# TOP.net
KiCad netlist of a schematic drawn in Altium Designer
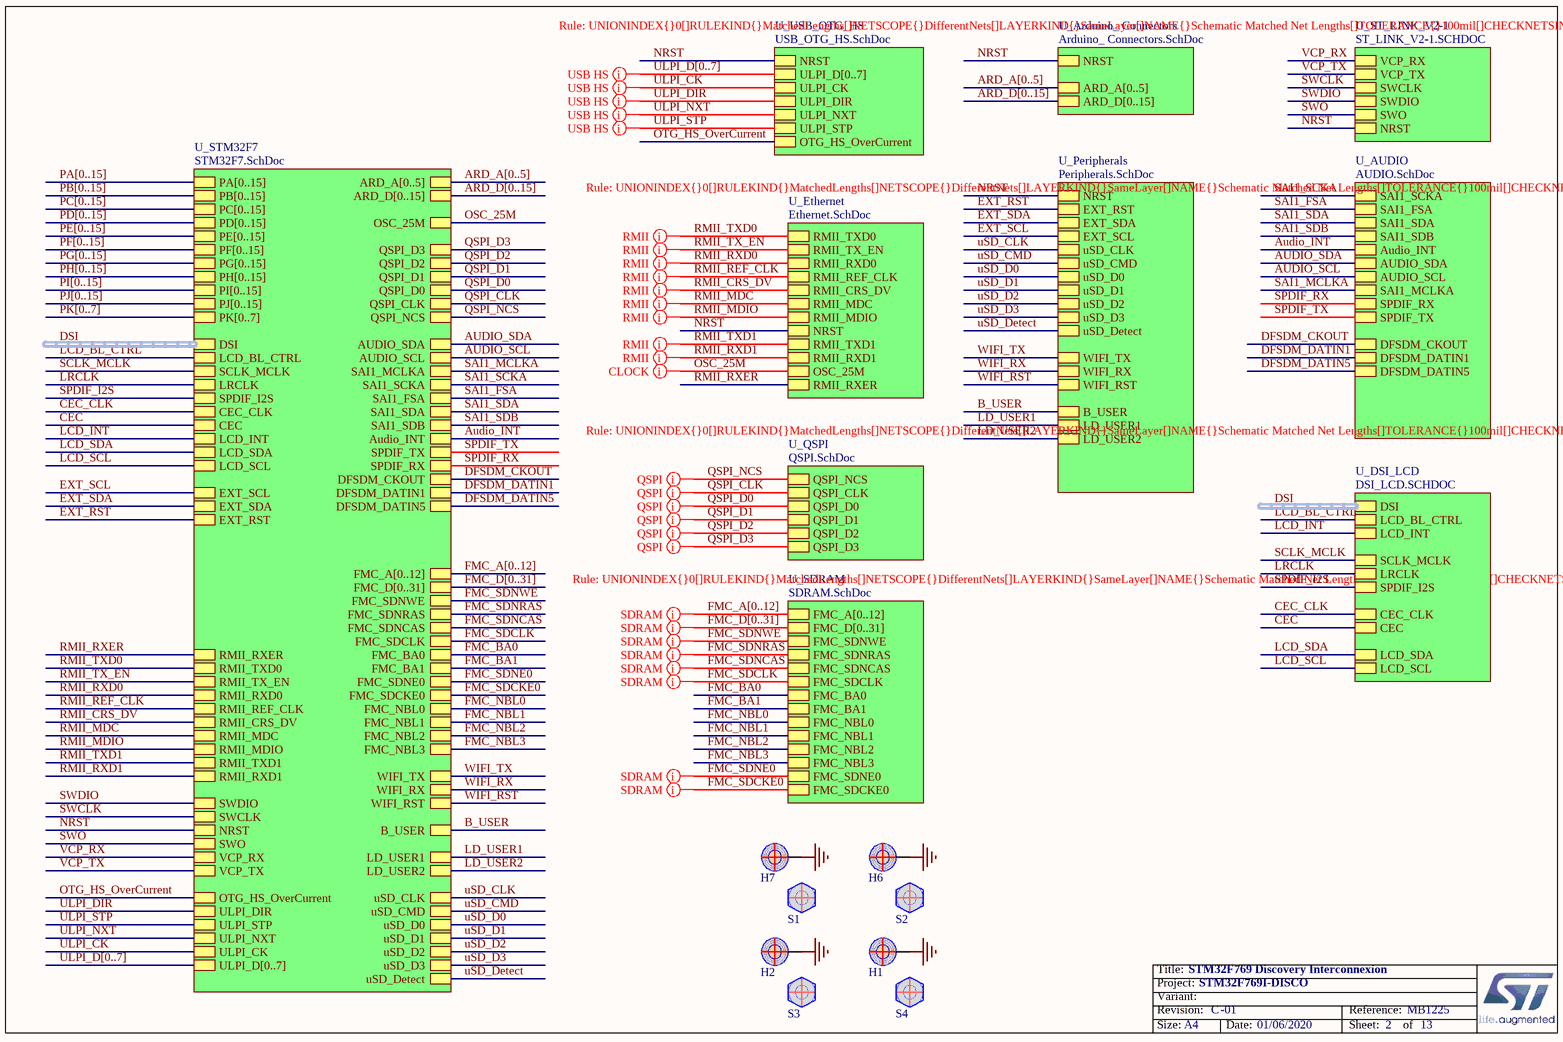
[diagram p0: TOP.SchDoc]

(export (version "E")
  (design (tool "Eeschema 10.0.6"))
  (components
    (comp (ref "H1")
      (value "POSITION HOLE C6D3R5")
      (footprint "HOLE_C6D3R5")
      (libsource (lib "MCD_TOOLS_MISCELLANEOUS") (part "POSITION HOLE C6D3R5"))
    )
    (comp (ref "H2")
      (value "POSITION HOLE C6D3R5")
      (footprint "HOLE_C6D3R5")
      (libsource (lib "MCD_TOOLS_MISCELLANEOUS") (part "POSITION HOLE C6D3R5"))
    )
    (comp (ref "H6")
      (value "POSITION HOLE C6D3R5")
      (footprint "HOLE_C6D3R5")
      (libsource (lib "MCD_TOOLS_MISCELLANEOUS") (part "POSITION HOLE C6D3R5"))
    )
    (comp (ref "H7")
      (value "POSITION HOLE C6D3R5")
      (footprint "HOLE_C6D3R5")
      (libsource (lib "MCD_TOOLS_MISCELLANEOUS") (part "POSITION HOLE C6D3R5"))
    )
    (comp (ref "S1")
      (value "Nylon Screw/Spacer M3x12.7")
      (description "Nylon Screw M3 and Spacer 12.7")
      (fields (field (name "PROVIDED") "Sub Co"))
      (libsource (lib "MCD_TOOLS_MISCELLANEOUS") (part "Nylon_ScrewM3_Spacer_12.7"))
    )
    (comp (ref "S2")
      (value "Nylon Screw/Spacer M3x12.7")
      (description "Nylon Screw M3 and Spacer 12.7")
      (fields (field (name "PROVIDED") "Sub Co"))
      (libsource (lib "MCD_TOOLS_MISCELLANEOUS") (part "Nylon_ScrewM3_Spacer_12.7"))
    )
    (comp (ref "S3")
      (value "Nylon Screw/Spacer M3x12.7")
      (description "Nylon Screw M3 and Spacer 12.7")
      (fields (field (name "PROVIDED") "Sub Co"))
      (libsource (lib "MCD_TOOLS_MISCELLANEOUS") (part "Nylon_ScrewM3_Spacer_12.7"))
    )
    (comp (ref "S4")
      (value "Nylon Screw/Spacer M3x12.7")
      (description "Nylon Screw M3 and Spacer 12.7")
      (fields (field (name "PROVIDED") "Sub Co"))
      (libsource (lib "MCD_TOOLS_MISCELLANEOUS") (part "Nylon_ScrewM3_Spacer_12.7"))
    )
  )
  (nets
    (net (code "340") (name "GND") (class "Default")
      (node (ref "H1") (pin "1") (pinfunction "1_1") (pintype "passive"))
      (node (ref "H2") (pin "1") (pinfunction "1_1") (pintype "passive"))
      (node (ref "H6") (pin "1") (pinfunction "1_1") (pintype "passive"))
      (node (ref "H7") (pin "1") (pinfunction "1_1") (pintype "passive"))
    )
  )
)
